# Controles.net
KiCad netlist of a schematic drawn in Altium Designer
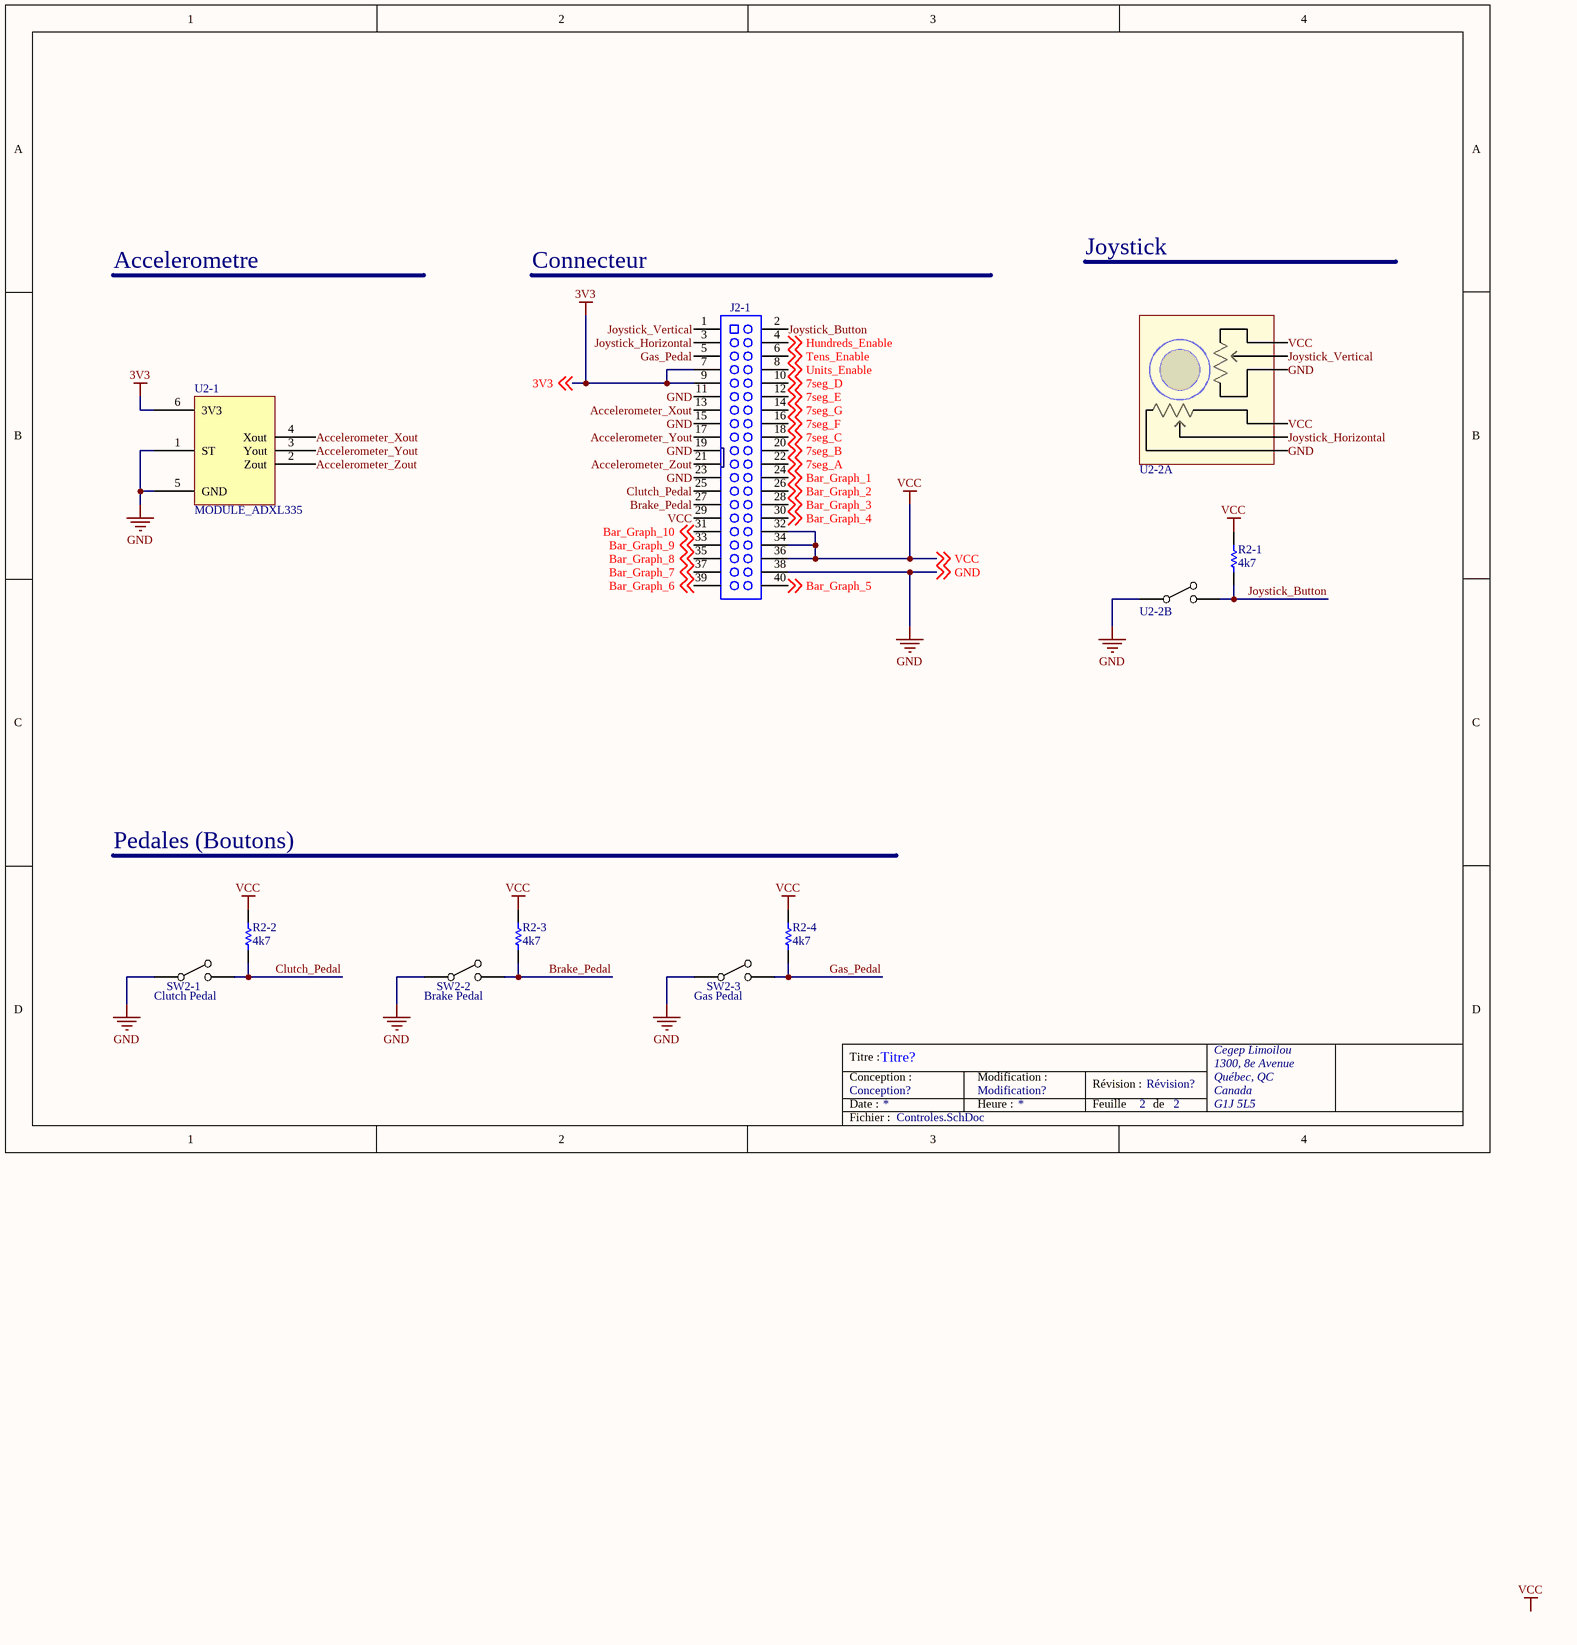
[diagram p0: Controles.SchDoc]

(export (version "E")
  (design (tool "Eeschema 10.0.6"))
  (components
    (comp (ref "J2-1")
      (value "Header")
      (footprint "CONN_HDR_100mils_2x20")
      (description "IDC Boxed Header, Straight, PCB Mount, Polarised, 40 Way, 2x20, 0.1\" Pitch")
      (fields (field (name "MFG") "Sullins"))
      (libsource (lib "LibEtudiants") (part "CONN_DUALROW_2x20"))
    )
    (comp (ref "R2-1")
      (value "4k7")
      (footprint "AXIAL-0.3")
      (description "Resistor")
      (fields (field (name "Comment") "Res1") (field (name "PUBLISHER") "Altium Limited"))
      (libsource (lib "Miscellaneous Devices") (part "Res1"))
    )
    (comp (ref "R2-2")
      (value "4k7")
      (footprint "AXIAL-0.3")
      (description "Resistor")
      (fields (field (name "Comment") "Res1") (field (name "PUBLISHER") "Altium Limited"))
      (libsource (lib "Miscellaneous Devices") (part "Res1"))
    )
    (comp (ref "R2-3")
      (value "4k7")
      (footprint "AXIAL-0.3")
      (description "Resistor")
      (fields (field (name "Comment") "Res1") (field (name "PUBLISHER") "Altium Limited"))
      (libsource (lib "Miscellaneous Devices") (part "Res1"))
    )
    (comp (ref "R2-4")
      (value "4k7")
      (footprint "AXIAL-0.3")
      (description "Resistor")
      (fields (field (name "Comment") "Res1") (field (name "PUBLISHER") "Altium Limited"))
      (libsource (lib "Miscellaneous Devices") (part "Res1"))
    )
    (comp (ref "SW2-1")
      (value "Clutch Pedal")
      (footprint "BUTTON_SPST_WS-TATV")
      (description "SPST Button")
      (fields (field (name "MFG") "Wurth"))
      (libsource (lib "LibEtudiants") (part "BTN_SPST"))
    )
    (comp (ref "SW2-2")
      (value "Brake Pedal")
      (footprint "BUTTON_SPST_WS-TATV")
      (description "SPST Button")
      (fields (field (name "MFG") "Wurth"))
      (libsource (lib "LibEtudiants") (part "BTN_SPST"))
    )
    (comp (ref "SW2-3")
      (value "Gas Pedal")
      (footprint "BUTTON_SPST_WS-TATV")
      (description "SPST Button")
      (fields (field (name "MFG") "Wurth"))
      (libsource (lib "LibEtudiants") (part "BTN_SPST"))
    )
    (comp (ref "U2-1")
      (value "MODULE_ADXL335")
      (footprint "MODULE_ADXL335")
      (description "Accelerometre")
      (libsource (lib "Schlib1") (part "MODULE_ADXL335"))
    )
    (comp (ref "U2-2")
      (value "Dual-axis joystick")
      (footprint "BTN_JOYSTICK_COM-09032")
      (description "Joystick deux-axes, sorties \"potentiometres\"")
      (fields (field (name "MFG") "Sparkfun"))
      (libsource (lib "LibEtudiants") (part "BTN_JOYSTICK_COM-09032"))
    )
  )
  (nets
    (net (code "1") (name "/Accelerometer_Xout") (class "Default")
      (node (ref "J2-1") (pin "13") (pinfunction "13_13") (pintype "passive"))
      (node (ref "U2-1") (pin "4") (pinfunction "Xout_4") (pintype "passive"))
    )
    (net (code "2") (name "/Accelerometer_Yout") (class "Default")
      (node (ref "J2-1") (pin "17") (pinfunction "17_17") (pintype "passive"))
      (node (ref "U2-1") (pin "3") (pinfunction "Yout_3") (pintype "passive"))
    )
    (net (code "3") (name "/Accelerometer_Zout") (class "Default")
      (node (ref "J2-1") (pin "21") (pinfunction "21_21") (pintype "passive"))
      (node (ref "U2-1") (pin "2") (pinfunction "Zout_2") (pintype "passive"))
    )
    (net (code "4") (name "/Brake_Pedal") (class "Default")
      (node (ref "J2-1") (pin "27") (pinfunction "27_27") (pintype "passive"))
      (node (ref "R2-3") (pin "1") (pinfunction "1_1") (pintype "passive"))
      (node (ref "SW2-2") (pin "2") (pintype "passive"))
    )
    (net (code "5") (name "/Clutch_Pedal") (class "Default")
      (node (ref "J2-1") (pin "25") (pinfunction "25_25") (pintype "passive"))
      (node (ref "R2-2") (pin "1") (pinfunction "1_1") (pintype "passive"))
      (node (ref "SW2-1") (pin "2") (pintype "passive"))
    )
    (net (code "6") (name "/Gas_Pedal") (class "Default")
      (node (ref "J2-1") (pin "5") (pinfunction "5_5") (pintype "passive"))
      (node (ref "R2-4") (pin "1") (pinfunction "1_1") (pintype "passive"))
      (node (ref "SW2-3") (pin "2") (pintype "passive"))
    )
    (net (code "7") (name "/Joystick_Button") (class "Default")
      (node (ref "J2-1") (pin "2") (pinfunction "2_2") (pintype "passive"))
      (node (ref "R2-1") (pin "1") (pinfunction "1_1") (pintype "passive"))
      (node (ref "U2-2") (pin "SW_B") (pinfunction "B_SW_B") (pintype "passive"))
    )
    (net (code "8") (name "/Joystick_Horizontal") (class "Default")
      (node (ref "J2-1") (pin "3") (pinfunction "3_3") (pintype "passive"))
      (node (ref "U2-2") (pin "X2") (pinfunction "W_X2") (pintype "passive"))
    )
    (net (code "9") (name "/Joystick_Vertical") (class "Default")
      (node (ref "J2-1") (pin "1") (pinfunction "1_1") (pintype "passive"))
      (node (ref "U2-2") (pin "Y2") (pinfunction "W_Y2") (pintype "passive"))
    )
    (net (code "10") (name "3V3") (class "Default")
      (node (ref "J2-1") (pin "7") (pinfunction "7_7") (pintype "passive"))
      (node (ref "J2-1") (pin "9") (pinfunction "9_9") (pintype "passive"))
      (node (ref "U2-1") (pin "6") (pinfunction "3V3_6") (pintype "passive"))
    )
    (net (code "11") (name "7seg_A") (class "Default")
      (node (ref "J2-1") (pin "22") (pinfunction "22_22") (pintype "passive"))
    )
    (net (code "12") (name "7seg_B") (class "Default")
      (node (ref "J2-1") (pin "20") (pinfunction "20_20") (pintype "passive"))
    )
    (net (code "13") (name "7seg_C") (class "Default")
      (node (ref "J2-1") (pin "18") (pinfunction "18_18") (pintype "passive"))
    )
    (net (code "14") (name "7seg_D") (class "Default")
      (node (ref "J2-1") (pin "10") (pinfunction "10_10") (pintype "passive"))
    )
    (net (code "15") (name "7seg_E") (class "Default")
      (node (ref "J2-1") (pin "12") (pinfunction "12_12") (pintype "passive"))
    )
    (net (code "16") (name "7seg_F") (class "Default")
      (node (ref "J2-1") (pin "16") (pinfunction "16_16") (pintype "passive"))
    )
    (net (code "17") (name "7seg_G") (class "Default")
      (node (ref "J2-1") (pin "14") (pinfunction "14_14") (pintype "passive"))
    )
    (net (code "18") (name "Bar_Graph_1") (class "Default")
      (node (ref "J2-1") (pin "24") (pinfunction "24_24") (pintype "passive"))
    )
    (net (code "19") (name "Bar_Graph_2") (class "Default")
      (node (ref "J2-1") (pin "26") (pinfunction "26_26") (pintype "passive"))
    )
    (net (code "20") (name "Bar_Graph_3") (class "Default")
      (node (ref "J2-1") (pin "28") (pinfunction "28_28") (pintype "passive"))
    )
    (net (code "21") (name "Bar_Graph_4") (class "Default")
      (node (ref "J2-1") (pin "30") (pinfunction "30_30") (pintype "passive"))
    )
    (net (code "22") (name "Bar_Graph_5") (class "Default")
      (node (ref "J2-1") (pin "40") (pinfunction "40_40") (pintype "passive"))
    )
    (net (code "23") (name "Bar_Graph_6") (class "Default")
      (node (ref "J2-1") (pin "39") (pinfunction "39_39") (pintype "passive"))
    )
    (net (code "24") (name "Bar_Graph_7") (class "Default")
      (node (ref "J2-1") (pin "37") (pinfunction "37_37") (pintype "passive"))
    )
    (net (code "25") (name "Bar_Graph_8") (class "Default")
      (node (ref "J2-1") (pin "35") (pinfunction "35_35") (pintype "passive"))
    )
    (net (code "26") (name "Bar_Graph_9") (class "Default")
      (node (ref "J2-1") (pin "33") (pinfunction "33_33") (pintype "passive"))
    )
    (net (code "27") (name "Bar_Graph_10") (class "Default")
      (node (ref "J2-1") (pin "31") (pinfunction "31_31") (pintype "passive"))
    )
    (net (code "28") (name "GND") (class "Default")
      (node (ref "J2-1") (pin "11") (pinfunction "11_11") (pintype "passive"))
      (node (ref "J2-1") (pin "15") (pinfunction "15_15") (pintype "passive"))
      (node (ref "J2-1") (pin "19") (pinfunction "19_19") (pintype "passive"))
      (node (ref "J2-1") (pin "23") (pinfunction "23_23") (pintype "passive"))
      (node (ref "J2-1") (pin "38") (pinfunction "38_38") (pintype "passive"))
      (node (ref "SW2-1") (pin "1") (pintype "passive"))
      (node (ref "SW2-2") (pin "1") (pintype "passive"))
      (node (ref "SW2-3") (pin "1") (pintype "passive"))
      (node (ref "U2-1") (pin "1") (pinfunction "ST_1") (pintype "passive"))
      (node (ref "U2-1") (pin "5") (pinfunction "GND_5") (pintype "passive"))
      (node (ref "U2-2") (pin "SW_A") (pinfunction "A_SW_A") (pintype "passive"))
      (node (ref "U2-2") (pin "X1") (pinfunction "CCW_X1") (pintype "passive"))
      (node (ref "U2-2") (pin "Y1") (pinfunction "CCW_Y1") (pintype "passive"))
    )
    (net (code "29") (name "Hundreds_Enable") (class "Default")
      (node (ref "J2-1") (pin "4") (pinfunction "4_4") (pintype "passive"))
    )
    (net (code "30") (name "Tens_Enable") (class "Default")
      (node (ref "J2-1") (pin "6") (pinfunction "6_6") (pintype "passive"))
    )
    (net (code "31") (name "Units_Enable") (class "Default")
      (node (ref "J2-1") (pin "8") (pinfunction "8_8") (pintype "passive"))
    )
    (net (code "32") (name "VCC") (class "Default")
      (node (ref "J2-1") (pin "29") (pinfunction "29_29") (pintype "passive"))
      (node (ref "J2-1") (pin "32") (pinfunction "32_32") (pintype "passive"))
      (node (ref "J2-1") (pin "34") (pinfunction "34_34") (pintype "passive"))
      (node (ref "J2-1") (pin "36") (pinfunction "36_36") (pintype "passive"))
      (node (ref "R2-1") (pin "2") (pinfunction "2_2") (pintype "passive"))
      (node (ref "R2-2") (pin "2") (pinfunction "2_2") (pintype "passive"))
      (node (ref "R2-3") (pin "2") (pinfunction "2_2") (pintype "passive"))
      (node (ref "R2-4") (pin "2") (pinfunction "2_2") (pintype "passive"))
      (node (ref "U2-2") (pin "X3") (pinfunction "CW_X3") (pintype "passive"))
      (node (ref "U2-2") (pin "Y3") (pinfunction "CW_Y3") (pintype "passive"))
    )
  )
)
